# RoboclawAdapter.net
KiCad netlist of a schematic drawn in EAGLE
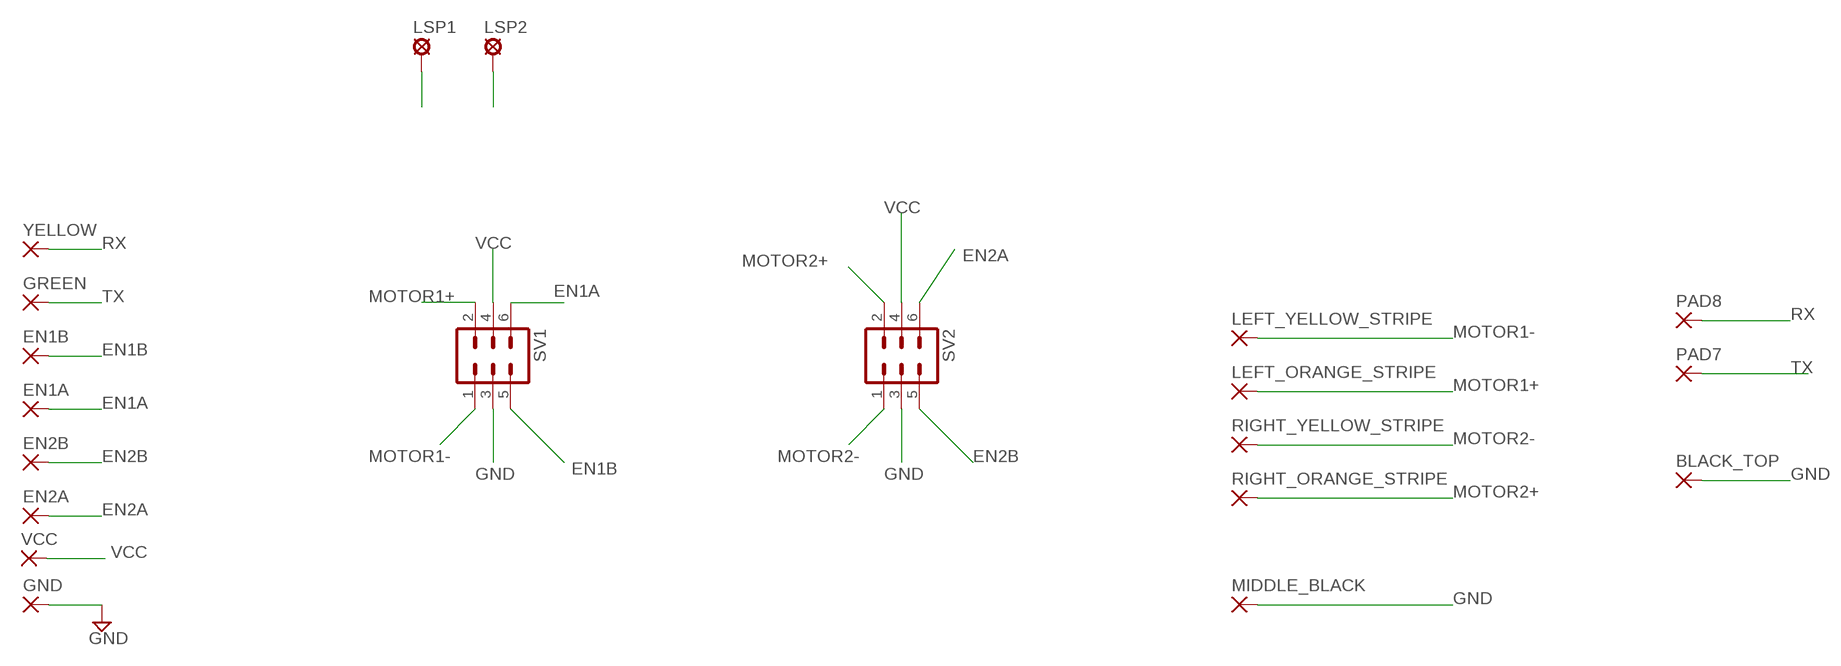
[diagram p0: schematic, sheet 1]

(export (version "E")
  (design (tool "Eeschema 10.0.6"))
  (components
    (comp (ref "BLACK_TOP")
      (value "2,54/0,9")
      (footprint "eagle-import:2,54_0,9")
      (libsource (lib "eagle-import") (part "2,54/0,9"))
    )
    (comp (ref "EN1A")
      (value "2,54/0,9")
      (footprint "eagle-import:2,54_0,9")
      (libsource (lib "eagle-import") (part "2,54/0,9"))
    )
    (comp (ref "EN1B")
      (value "2,54/0,9")
      (footprint "eagle-import:2,54_0,9")
      (libsource (lib "eagle-import") (part "2,54/0,9"))
    )
    (comp (ref "EN2A")
      (value "2,54/0,9")
      (footprint "eagle-import:2,54_0,9")
      (libsource (lib "eagle-import") (part "2,54/0,9"))
    )
    (comp (ref "EN2B")
      (value "2,54/0,9")
      (footprint "eagle-import:2,54_0,9")
      (libsource (lib "eagle-import") (part "2,54/0,9"))
    )
    (comp (ref "GND")
      (value "2,54/0,9")
      (footprint "eagle-import:2,54_0,9")
      (libsource (lib "eagle-import") (part "2,54/0,9"))
    )
    (comp (ref "GREEN")
      (value "2,54/0,9")
      (footprint "eagle-import:2,54_0,9")
      (libsource (lib "eagle-import") (part "2,54/0,9"))
    )
    (comp (ref "LEFT_ORANGE_STRIPE")
      (value "2,54/0,9")
      (footprint "eagle-import:2,54_0,9")
      (libsource (lib "eagle-import") (part "2,54/0,9"))
    )
    (comp (ref "LEFT_YELLOW_STRIPE")
      (value "2,54/0,9")
      (footprint "eagle-import:2,54_0,9")
      (libsource (lib "eagle-import") (part "2,54/0,9"))
    )
    (comp (ref "LSP1")
      (value "SE14")
      (footprint "eagle-import:SE14")
      (libsource (lib "eagle-import") (part "SE14"))
    )
    (comp (ref "LSP2")
      (value "SE14")
      (footprint "eagle-import:SE14")
      (libsource (lib "eagle-import") (part "SE14"))
    )
    (comp (ref "MIDDLE_BLACK")
      (value "2,54/0,9")
      (footprint "eagle-import:2,54_0,9")
      (libsource (lib "eagle-import") (part "2,54/0,9"))
    )
    (comp (ref "PAD7")
      (value "2,54/0,9")
      (footprint "eagle-import:2,54_0,9")
      (libsource (lib "eagle-import") (part "2,54/0,9"))
    )
    (comp (ref "PAD8")
      (value "2,54/0,9")
      (footprint "eagle-import:2,54_0,9")
      (libsource (lib "eagle-import") (part "2,54/0,9"))
    )
    (comp (ref "RIGHT_ORANGE_STRIPE")
      (value "2,54/0,9")
      (footprint "eagle-import:2,54_0,9")
      (libsource (lib "eagle-import") (part "2,54/0,9"))
    )
    (comp (ref "RIGHT_YELLOW_STRIPE")
      (value "2,54/0,9")
      (footprint "eagle-import:2,54_0,9")
      (libsource (lib "eagle-import") (part "2,54/0,9"))
    )
    (comp (ref "SV1")
      (value "MA03-2")
      (footprint "eagle-import:MA03-2")
      (libsource (lib "eagle-import") (part "MA03-2"))
    )
    (comp (ref "SV2")
      (value "MA03-2")
      (footprint "eagle-import:MA03-2")
      (libsource (lib "eagle-import") (part "MA03-2"))
    )
    (comp (ref "VCC")
      (value "2,54/0,9")
      (footprint "eagle-import:2,54_0,9")
      (libsource (lib "eagle-import") (part "2,54/0,9"))
    )
    (comp (ref "YELLOW")
      (value "2,54/0,9")
      (footprint "eagle-import:2,54_0,9")
      (libsource (lib "eagle-import") (part "2,54/0,9"))
    )
  )
  (nets
    (net (code "1") (name "/EN1A") (class "Default")
      (node (ref "EN1A") (pin "1") (pinfunction "P_1") (pintype "passive"))
      (node (ref "SV1") (pin "6") (pinfunction "6_6") (pintype "passive"))
    )
    (net (code "2") (name "/EN1B") (class "Default")
      (node (ref "EN1B") (pin "1") (pinfunction "P_1") (pintype "passive"))
      (node (ref "SV1") (pin "5") (pinfunction "5_5") (pintype "passive"))
    )
    (net (code "3") (name "/EN2A") (class "Default")
      (node (ref "EN2A") (pin "1") (pinfunction "P_1") (pintype "passive"))
      (node (ref "SV2") (pin "6") (pinfunction "6_6") (pintype "passive"))
    )
    (net (code "4") (name "/EN2B") (class "Default")
      (node (ref "EN2B") (pin "1") (pinfunction "P_1") (pintype "passive"))
      (node (ref "SV2") (pin "5") (pinfunction "5_5") (pintype "passive"))
    )
    (net (code "5") (name "/MOTOR1+") (class "Default")
      (node (ref "LEFT_ORANGE_STRIPE") (pin "1") (pinfunction "P_1") (pintype "passive"))
      (node (ref "SV1") (pin "2") (pinfunction "2_2") (pintype "passive"))
    )
    (net (code "6") (name "/MOTOR1-") (class "Default")
      (node (ref "LEFT_YELLOW_STRIPE") (pin "1") (pinfunction "P_1") (pintype "passive"))
      (node (ref "SV1") (pin "1") (pinfunction "1_1") (pintype "passive"))
    )
    (net (code "7") (name "/MOTOR2+") (class "Default")
      (node (ref "RIGHT_ORANGE_STRIPE") (pin "1") (pinfunction "P_1") (pintype "passive"))
      (node (ref "SV2") (pin "2") (pinfunction "2_2") (pintype "passive"))
    )
    (net (code "8") (name "/MOTOR2-") (class "Default")
      (node (ref "RIGHT_YELLOW_STRIPE") (pin "1") (pinfunction "P_1") (pintype "passive"))
      (node (ref "SV2") (pin "1") (pinfunction "1_1") (pintype "passive"))
    )
    (net (code "9") (name "/RX") (class "Default")
      (node (ref "PAD8") (pin "1") (pinfunction "P_1") (pintype "passive"))
      (node (ref "YELLOW") (pin "1") (pinfunction "P_1") (pintype "passive"))
    )
    (net (code "10") (name "/TX") (class "Default")
      (node (ref "GREEN") (pin "1") (pinfunction "P_1") (pintype "passive"))
      (node (ref "PAD7") (pin "1") (pinfunction "P_1") (pintype "passive"))
    )
    (net (code "11") (name "/VCC") (class "Default")
      (node (ref "SV1") (pin "4") (pinfunction "4_4") (pintype "passive"))
      (node (ref "SV2") (pin "4") (pinfunction "4_4") (pintype "passive"))
      (node (ref "VCC") (pin "1") (pinfunction "P_1") (pintype "passive"))
    )
    (net (code "12") (name "/VCC12") (class "Default")
      (node (ref "LSP1") (pin "MP") (pinfunction "MP_MP") (pintype "passive"))
      (node (ref "LSP2") (pin "MP") (pinfunction "MP_MP") (pintype "passive"))
    )
    (net (code "13") (name "GND") (class "Default")
      (node (ref "BLACK_TOP") (pin "1") (pinfunction "P_1") (pintype "passive"))
      (node (ref "GND") (pin "1") (pinfunction "P_1") (pintype "passive"))
      (node (ref "MIDDLE_BLACK") (pin "1") (pinfunction "P_1") (pintype "passive"))
      (node (ref "SV1") (pin "3") (pinfunction "3_3") (pintype "passive"))
      (node (ref "SV2") (pin "3") (pinfunction "3_3") (pintype "passive"))
    )
  )
)
